# MiniSTM32_1.net
KiCad netlist of a schematic drawn in Altium Designer
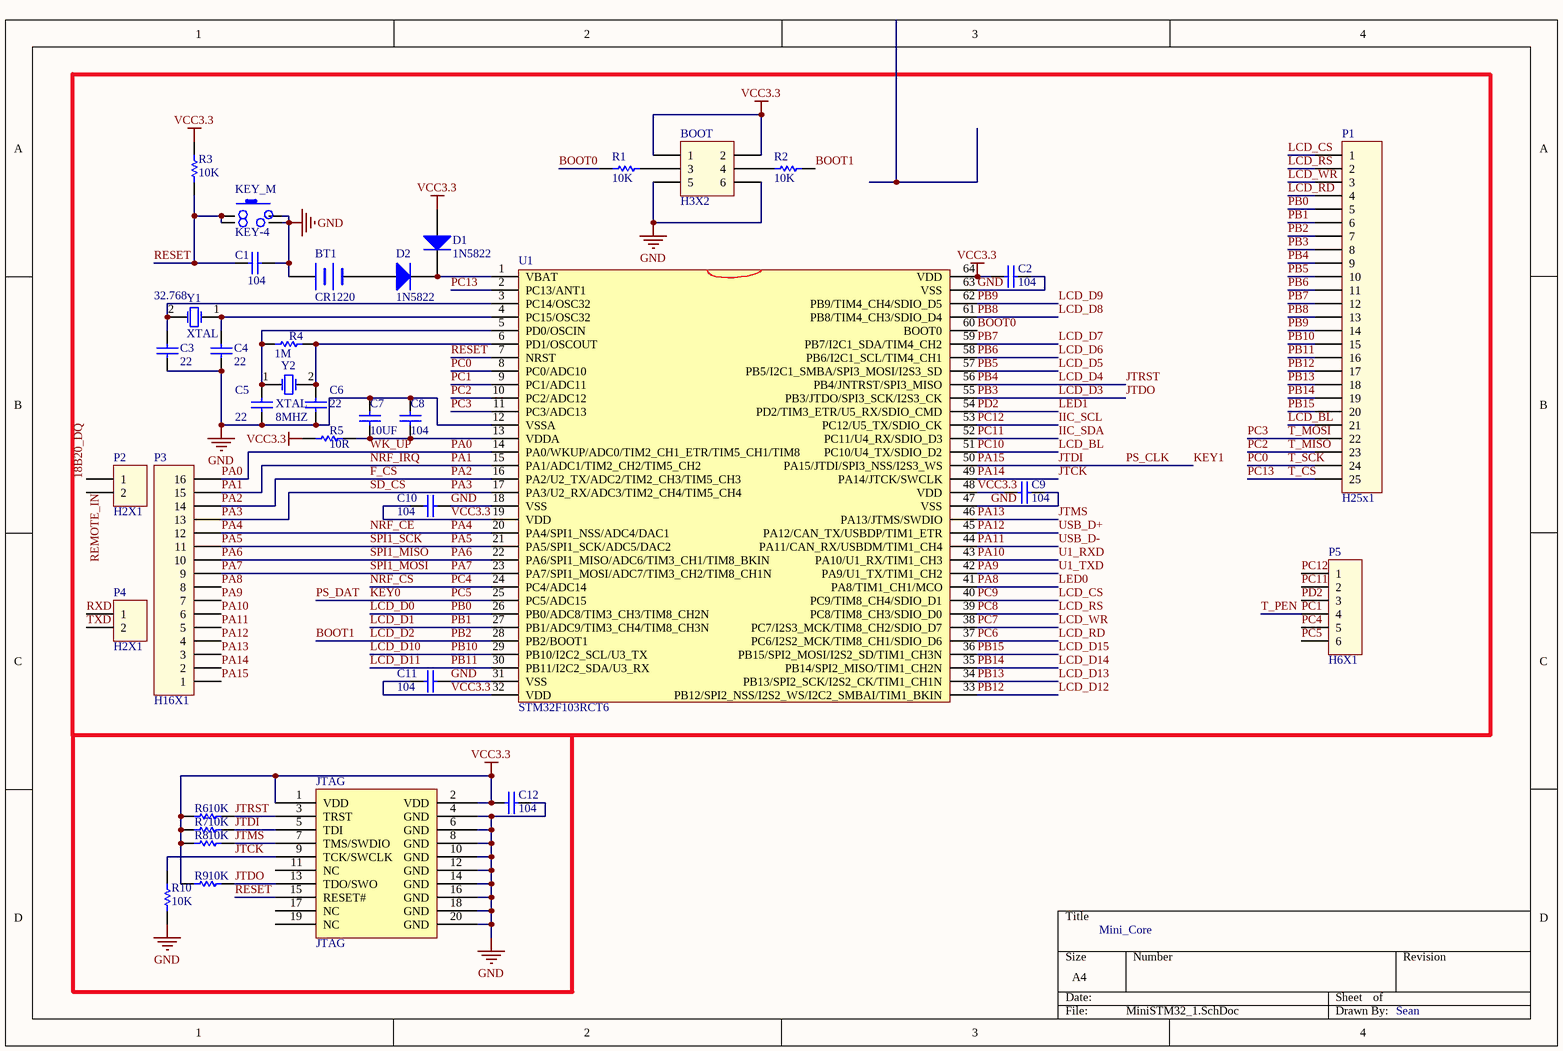
[diagram p0: MiniSTM32_1.SchDoc]

(export (version "E")
  (design (tool "Eeschema 10.0.6"))
  (components
    (comp (ref "BOOT") (value "H3X2") (footprint "H2.54-2X3") (libsource (lib "Sean") (part "H3X2")))
    (comp (ref "BT1") (value "CR1220") (footprint "CR1220") (libsource (lib "Sean") (part "BATTERY")))
    (comp (ref "C1")
      (value "Cap")
      (footprint "CAP[0603]")
      (fields (field (name "ALTIUM_UNNAMED_1") "104"))
      (libsource (lib "Sean") (part "Cap"))
    )
    (comp (ref "C2")
      (value "Cap")
      (footprint "CAP[0603]")
      (fields (field (name "ALTIUM_UNNAMED_1") "104"))
      (libsource (lib "Sean") (part "Cap"))
    )
    (comp (ref "C3")
      (value "Cap")
      (footprint "CAP[0603]")
      (fields (field (name "ALTIUM_UNNAMED_1") "22"))
      (libsource (lib "Sean") (part "Cap"))
    )
    (comp (ref "C4")
      (value "Cap")
      (footprint "CAP[0603]")
      (fields (field (name "ALTIUM_UNNAMED_1") "22"))
      (libsource (lib "Sean") (part "Cap"))
    )
    (comp (ref "C5")
      (value "Cap")
      (footprint "CAP[0805]")
      (fields (field (name "ALTIUM_UNNAMED_1") "22"))
      (libsource (lib "Sean") (part "Cap"))
    )
    (comp (ref "C6")
      (value "Cap")
      (footprint "CAP[0805]")
      (fields (field (name "ALTIUM_UNNAMED_1") "22"))
      (libsource (lib "Sean") (part "Cap"))
    )
    (comp (ref "C7")
      (value "Cap")
      (footprint "CAP[1206]")
      (fields (field (name "ALTIUM_UNNAMED_1") "10UF"))
      (libsource (lib "Sean") (part "Cap"))
    )
    (comp (ref "C8")
      (value "Cap")
      (footprint "CAP[0603]")
      (fields (field (name "ALTIUM_UNNAMED_1") "104"))
      (libsource (lib "Sean") (part "Cap"))
    )
    (comp (ref "C9")
      (value "Cap")
      (footprint "CAP[0603]")
      (fields (field (name "ALTIUM_UNNAMED_1") "104"))
      (libsource (lib "Sean") (part "Cap"))
    )
    (comp (ref "C10")
      (value "Cap")
      (footprint "CAP[0603]")
      (fields (field (name "ALTIUM_UNNAMED_1") "104"))
      (libsource (lib "Sean") (part "Cap"))
    )
    (comp (ref "C11")
      (value "Cap")
      (footprint "CAP[0603]")
      (fields (field (name "ALTIUM_UNNAMED_1") "104"))
      (libsource (lib "Sean") (part "Cap"))
    )
    (comp (ref "C12")
      (value "Cap")
      (footprint "CAP[0603]")
      (fields (field (name "ALTIUM_UNNAMED_1") "104"))
      (libsource (lib "Sean") (part "Cap"))
    )
    (comp (ref "D1") (value "1N5822") (footprint "1N4733") (libsource (lib "Sean") (part "1N5822")))
    (comp (ref "D2") (value "1N5822") (footprint "1N4733") (libsource (lib "Sean") (part "1N5822")))
    (comp (ref "JTAG") (value "JTAG") (footprint "JTAG") (libsource (lib "Sean") (part "JTAG")))
    (comp (ref "KEY_M") (value "KEY-4") (footprint "KEY-4(DIP)") (libsource (lib "Sean") (part "KEY-4")))
    (comp (ref "P1") (value "H25x1") (footprint "H2.54-1X25") (libsource (lib "Sean") (part "H25x1")))
    (comp (ref "P2") (value "H2X1") (footprint "H2.54-1X2") (libsource (lib "Sean") (part "H2X1")))
    (comp (ref "P3") (value "H16X1") (footprint "H2.54-1X16") (libsource (lib "Sean") (part "H16X1")))
    (comp (ref "P4") (value "H2X1") (footprint "H2.54-1X2") (libsource (lib "Sean") (part "H2X1")))
    (comp (ref "P5") (value "H6X1") (footprint "H2.54-1X6") (libsource (lib "Sean") (part "H6X1")))
    (comp (ref "R1")
      (value "Res")
      (footprint "RES[0603]")
      (fields (field (name "ALTIUM_UNNAMED_1") "10K"))
      (libsource (lib "Sean") (part "Res"))
    )
    (comp (ref "R2")
      (value "Res")
      (footprint "RES[0603]")
      (fields (field (name "ALTIUM_UNNAMED_1") "10K"))
      (libsource (lib "Sean") (part "Res"))
    )
    (comp (ref "R3")
      (value "Res")
      (footprint "RES[0603]")
      (fields (field (name "ALTIUM_UNNAMED_1") "10K"))
      (libsource (lib "Sean") (part "Res"))
    )
    (comp (ref "R4")
      (value "Res")
      (footprint "RES[0603]")
      (fields (field (name "ALTIUM_UNNAMED_1") "1M"))
      (libsource (lib "Sean") (part "Res"))
    )
    (comp (ref "R5")
      (value "Res")
      (footprint "RES[0603]")
      (fields (field (name "ALTIUM_UNNAMED_1") "10R"))
      (libsource (lib "Sean") (part "Res"))
    )
    (comp (ref "R6")
      (value "Res")
      (footprint "RES[0603]")
      (fields (field (name "ALTIUM_UNNAMED_1") "10K"))
      (libsource (lib "Sean") (part "Res"))
    )
    (comp (ref "R7")
      (value "Res")
      (footprint "RES[0603]")
      (fields (field (name "ALTIUM_UNNAMED_1") "10K"))
      (libsource (lib "Sean") (part "Res"))
    )
    (comp (ref "R8")
      (value "Res")
      (footprint "RES[0603]")
      (fields (field (name "ALTIUM_UNNAMED_1") "10K"))
      (libsource (lib "Sean") (part "Res"))
    )
    (comp (ref "R9")
      (value "Res")
      (footprint "RES[0603]")
      (fields (field (name "ALTIUM_UNNAMED_1") "10K"))
      (libsource (lib "Sean") (part "Res"))
    )
    (comp (ref "R10")
      (value "Res")
      (footprint "RES[0603]")
      (fields (field (name "ALTIUM_UNNAMED_1") "10K"))
      (libsource (lib "Sean") (part "Res"))
    )
    (comp (ref "U1")
      (value "STM32F103RCT6")
      (footprint "LQFP-64")
      (libsource (lib "Sean") (part "STM32F103RCT6"))
    )
    (comp (ref "Y1")
      (value "XTAL")
      (footprint "XTAL-32768_2")
      (fields (field (name "ALTIUM_UNNAMED_1") "32.768"))
      (libsource (lib "Sean") (part "XTAL"))
    )
    (comp (ref "Y2")
      (value "XTAL")
      (footprint "XTAL")
      (fields (field (name "ALTIUM_UNNAMED_1") "8MHZ"))
      (libsource (lib "Sean") (part "XTAL"))
    )
  )
  (nets
    (net (code "1") (name "/18B20_DQ") (class "Default")
      (node (ref "P2") (pin "1") (pinfunction "1_1") (pintype "passive"))
    )
    (net (code "2") (name "/BOOT0") (class "Default")
      (node (ref "R1") (pin "1") (pinfunction "1_1") (pintype "passive"))
      (node (ref "U1") (pin "60") (pinfunction "BOOT0_60") (pintype "passive"))
    )
    (net (code "3") (name "/BOOT1") (class "Default")
      (node (ref "P1") (pin "7") (pinfunction "7_7") (pintype "passive"))
      (node (ref "R2") (pin "2") (pinfunction "2_2") (pintype "passive"))
      (node (ref "U1") (pin "28") (pinfunction "PB2/BOOT1_28") (pintype "passive"))
    )
    (net (code "4") (name "/F_CS") (class "Default")
      (node (ref "P3") (pin "14") (pinfunction "14_14") (pintype "passive"))
      (node (ref "U1") (pin "16") (pinfunction "PA2/U2_TX/ADC2/TIM2_CH3/TIM5_CH3_16") (pintype "passive"))
    )
    (net (code "5") (name "/IIC_SCL") (class "Default")
      (node (ref "P5") (pin "1") (pinfunction "1_1") (pintype "passive"))
      (node (ref "U1") (pin "53") (pinfunction "PC12/U5_TX/SDIO_CK_53") (pintype "passive"))
    )
    (net (code "6") (name "/IIC_SDA") (class "Default")
      (node (ref "P5") (pin "2") (pinfunction "2_2") (pintype "passive"))
      (node (ref "U1") (pin "52") (pinfunction "PC11/U4_RX/SDIO_D3_52") (pintype "passive"))
    )
    (net (code "7") (name "/JTCK") (class "Default")
      (node (ref "JTAG") (pin "9") (pinfunction "TCK/SWCLK_9") (pintype "passive"))
      (node (ref "P3") (pin "2") (pinfunction "2_2") (pintype "passive"))
      (node (ref "R10") (pin "1") (pinfunction "1_1") (pintype "passive"))
      (node (ref "U1") (pin "49") (pinfunction "PA14/JTCK/SWCLK_49") (pintype "passive"))
    )
    (net (code "8") (name "/JTDI") (class "Default")
      (node (ref "JTAG") (pin "5") (pinfunction "TDI_5") (pintype "passive"))
      (node (ref "P3") (pin "1") (pinfunction "1_1") (pintype "passive"))
      (node (ref "R7") (pin "1") (pinfunction "1_1") (pintype "passive"))
      (node (ref "U1") (pin "50") (pinfunction "PA15/JTDI/SPI3_NSS/I2S3_WS_50") (pintype "passive"))
    )
    (net (code "9") (name "/JTDO") (class "Default")
      (node (ref "JTAG") (pin "13") (pinfunction "TDO/SWO_13") (pintype "passive"))
      (node (ref "P1") (pin "8") (pinfunction "8_8") (pintype "passive"))
      (node (ref "R9") (pin "1") (pinfunction "1_1") (pintype "passive"))
      (node (ref "U1") (pin "55") (pinfunction "PB3/JTDO/SPI3_SCK/I2S3_CK_55") (pintype "passive"))
    )
    (net (code "10") (name "/JTMS") (class "Default")
      (node (ref "JTAG") (pin "7") (pinfunction "TMS/SWDIO_7") (pintype "passive"))
      (node (ref "P3") (pin "3") (pinfunction "3_3") (pintype "passive"))
      (node (ref "R8") (pin "1") (pinfunction "1_1") (pintype "passive"))
      (node (ref "U1") (pin "46") (pinfunction "PA13/JTMS/SWDIO_46") (pintype "passive"))
    )
    (net (code "11") (name "/JTRST") (class "Default")
      (node (ref "JTAG") (pin "3") (pinfunction "TRST_3") (pintype "passive"))
      (node (ref "P1") (pin "9") (pinfunction "9_9") (pintype "passive"))
      (node (ref "R6") (pin "1") (pinfunction "1_1") (pintype "passive"))
      (node (ref "U1") (pin "56") (pinfunction "PB4/JNTRST/SPI3_MISO_56") (pintype "passive"))
    )
    (net (code "12") (name "/KEY0") (class "Default")
      (node (ref "P5") (pin "6") (pinfunction "6_6") (pintype "passive"))
      (node (ref "U1") (pin "25") (pinfunction "PC5/ADC15_25") (pintype "passive"))
    )
    (net (code "13") (name "/LCD_BL") (class "Default")
      (node (ref "P1") (pin "21") (pinfunction "21_21") (pintype "passive"))
      (node (ref "U1") (pin "51") (pinfunction "PC10/U4_TX/SDIO_D2_51") (pintype "passive"))
    )
    (net (code "14") (name "/LCD_CS") (class "Default")
      (node (ref "P1") (pin "1") (pinfunction "1_1") (pintype "passive"))
      (node (ref "U1") (pin "40") (pinfunction "PC9/TIM8_CH4/SDIO_D1_40") (pintype "passive"))
    )
    (net (code "15") (name "/LCD_D0") (class "Default")
      (node (ref "P1") (pin "5") (pinfunction "5_5") (pintype "passive"))
      (node (ref "U1") (pin "26") (pinfunction "PB0/ADC8/TIM3_CH3/TIM8_CH2N_26") (pintype "passive"))
    )
    (net (code "16") (name "/LCD_D1") (class "Default")
      (node (ref "P1") (pin "6") (pinfunction "6_6") (pintype "passive"))
      (node (ref "U1") (pin "27") (pinfunction "PB1/ADC9/TIM3_CH4/TIM8_CH3N_27") (pintype "passive"))
    )
    (net (code "17") (name "/LCD_D5") (class "Default")
      (node (ref "P1") (pin "10") (pinfunction "10_10") (pintype "passive"))
      (node (ref "U1") (pin "57") (pinfunction "PB5/I2C1_SMBA/SPI3_MOSI/I2S3_SD_57") (pintype "passive"))
    )
    (net (code "18") (name "/LCD_D6") (class "Default")
      (node (ref "P1") (pin "11") (pinfunction "11_11") (pintype "passive"))
      (node (ref "U1") (pin "58") (pinfunction "PB6/I2C1_SCL/TIM4_CH1_58") (pintype "passive"))
    )
    (net (code "19") (name "/LCD_D7") (class "Default")
      (node (ref "P1") (pin "12") (pinfunction "12_12") (pintype "passive"))
      (node (ref "U1") (pin "59") (pinfunction "PB7/I2C1_SDA/TIM4_CH2_59") (pintype "passive"))
    )
    (net (code "20") (name "/LCD_D8") (class "Default")
      (node (ref "P1") (pin "13") (pinfunction "13_13") (pintype "passive"))
      (node (ref "U1") (pin "61") (pinfunction "PB8/TIM4_CH3/SDIO_D4_61") (pintype "passive"))
    )
    (net (code "21") (name "/LCD_D9") (class "Default")
      (node (ref "P1") (pin "14") (pinfunction "14_14") (pintype "passive"))
      (node (ref "U1") (pin "62") (pinfunction "PB9/TIM4_CH4/SDIO_D5_62") (pintype "passive"))
    )
    (net (code "22") (name "/LCD_D10") (class "Default")
      (node (ref "P1") (pin "15") (pinfunction "15_15") (pintype "passive"))
      (node (ref "U1") (pin "29") (pinfunction "PB10/I2C2_SCL/U3_TX_29") (pintype "passive"))
    )
    (net (code "23") (name "/LCD_D11") (class "Default")
      (node (ref "P1") (pin "16") (pinfunction "16_16") (pintype "passive"))
      (node (ref "U1") (pin "30") (pinfunction "PB11/I2C2_SDA/U3_RX_30") (pintype "passive"))
    )
    (net (code "24") (name "/LCD_D12") (class "Default")
      (node (ref "P1") (pin "17") (pinfunction "17_17") (pintype "passive"))
      (node (ref "U1") (pin "33") (pinfunction "PB12/SPI2_NSS/I2S2_WS/I2C2_SMBAI/TIM1_BKIN_33") (pintype "passive"))
    )
    (net (code "25") (name "/LCD_D13") (class "Default")
      (node (ref "P1") (pin "18") (pinfunction "18_18") (pintype "passive"))
      (node (ref "U1") (pin "34") (pinfunction "PB13/SPI2_SCK/I2S2_CK/TIM1_CH1N_34") (pintype "passive"))
    )
    (net (code "26") (name "/LCD_D14") (class "Default")
      (node (ref "P1") (pin "19") (pinfunction "19_19") (pintype "passive"))
      (node (ref "U1") (pin "35") (pinfunction "PB14/SPI2_MISO/TIM1_CH2N_35") (pintype "passive"))
    )
    (net (code "27") (name "/LCD_D15") (class "Default")
      (node (ref "P1") (pin "20") (pinfunction "20_20") (pintype "passive"))
      (node (ref "U1") (pin "36") (pinfunction "PB15/SPI2_MOSI/I2S2_SD/TIM1_CH3N_36") (pintype "passive"))
    )
    (net (code "28") (name "/LCD_RD") (class "Default")
      (node (ref "P1") (pin "4") (pinfunction "4_4") (pintype "passive"))
      (node (ref "U1") (pin "37") (pinfunction "PC6/I2S2_MCK/TIM8_CH1/SDIO_D6_37") (pintype "passive"))
    )
    (net (code "29") (name "/LCD_RS") (class "Default")
      (node (ref "P1") (pin "2") (pinfunction "2_2") (pintype "passive"))
      (node (ref "U1") (pin "39") (pinfunction "PC8/TIM8_CH3/SDIO_D0_39") (pintype "passive"))
    )
    (net (code "30") (name "/LCD_WR") (class "Default")
      (node (ref "P1") (pin "3") (pinfunction "3_3") (pintype "passive"))
      (node (ref "U1") (pin "38") (pinfunction "PC7/I2S3_MCK/TIM8_CH2/SDIO_D7_38") (pintype "passive"))
    )
    (net (code "31") (name "/LED0") (class "Default")
      (node (ref "P3") (pin "8") (pinfunction "8_8") (pintype "passive"))
      (node (ref "U1") (pin "41") (pinfunction "PA8/TIM1_CH1/MCO_41") (pintype "passive"))
    )
    (net (code "32") (name "/LED1") (class "Default")
      (node (ref "P5") (pin "3") (pinfunction "3_3") (pintype "passive"))
      (node (ref "U1") (pin "54") (pinfunction "PD2/TIM3_ETR/U5_RX/SDIO_CMD_54") (pintype "passive"))
    )
    (net (code "33") (name "/NRF_CE") (class "Default")
      (node (ref "P3") (pin "12") (pinfunction "12_12") (pintype "passive"))
      (node (ref "U1") (pin "20") (pinfunction "PA4/SPI1_NSS/ADC4/DAC1_20") (pintype "passive"))
    )
    (net (code "34") (name "/NRF_CS") (class "Default")
      (node (ref "P5") (pin "5") (pinfunction "5_5") (pintype "passive"))
      (node (ref "U1") (pin "24") (pinfunction "PC4/ADC14_24") (pintype "passive"))
    )
    (net (code "35") (name "/NRF_IRQ") (class "Default")
      (node (ref "P3") (pin "15") (pinfunction "15_15") (pintype "passive"))
      (node (ref "U1") (pin "15") (pinfunction "PA1/ADC1/TIM2_CH2/TIM5_CH2_15") (pintype "passive"))
    )
    (net (code "36") (name "/PA0") (class "Default")
      (node (ref "P3") (pin "16") (pinfunction "16_16") (pintype "passive"))
      (node (ref "U1") (pin "14") (pinfunction "PA0/WKUP/ADC0/TIM2_CH1_ETR/TIM5_CH1/TIM8_14") (pintype "passive"))
    )
    (net (code "37") (name "/PA3") (class "Default")
      (node (ref "P3") (pin "13") (pinfunction "13_13") (pintype "passive"))
      (node (ref "U1") (pin "17") (pinfunction "PA3/U2_RX/ADC3/TIM2_CH4/TIM5_CH4_17") (pintype "passive"))
    )
    (net (code "38") (name "/PA5") (class "Default")
      (node (ref "P3") (pin "11") (pinfunction "11_11") (pintype "passive"))
      (node (ref "U1") (pin "21") (pinfunction "PA5/SPI1_SCK/ADC5/DAC2_21") (pintype "passive"))
    )
    (net (code "39") (name "/PA6") (class "Default")
      (node (ref "P3") (pin "10") (pinfunction "10_10") (pintype "passive"))
      (node (ref "U1") (pin "22") (pinfunction "PA6/SPI1_MISO/ADC6/TIM3_CH1/TIM8_BKIN_22") (pintype "passive"))
    )
    (net (code "40") (name "/PA7") (class "Default")
      (node (ref "P3") (pin "9") (pinfunction "9_9") (pintype "passive"))
      (node (ref "U1") (pin "23") (pinfunction "PA7/SPI1_MOSI/ADC7/TIM3_CH2/TIM8_CH1N_23") (pintype "passive"))
    )
    (net (code "41") (name "/PA9") (class "Default")
      (node (ref "P3") (pin "7") (pinfunction "7_7") (pintype "passive"))
      (node (ref "U1") (pin "42") (pinfunction "PA9/U1_TX/TIM1_CH2_42") (pintype "passive"))
    )
    (net (code "42") (name "/PA10") (class "Default")
      (node (ref "P3") (pin "6") (pinfunction "6_6") (pintype "passive"))
      (node (ref "U1") (pin "43") (pinfunction "PA10/U1_RX/TIM1_CH3_43") (pintype "passive"))
    )
    (net (code "43") (name "/PA11") (class "Default")
      (node (ref "P3") (pin "5") (pinfunction "5_5") (pintype "passive"))
      (node (ref "U1") (pin "44") (pinfunction "PA11/CAN_RX/USBDM/TIM1_CH4_44") (pintype "passive"))
    )
    (net (code "44") (name "/PA12") (class "Default")
      (node (ref "P3") (pin "4") (pinfunction "4_4") (pintype "passive"))
      (node (ref "U1") (pin "45") (pinfunction "PA12/CAN_TX/USBDP/TIM1_ETR_45") (pintype "passive"))
    )
    (net (code "45") (name "/PC0") (class "Default")
      (node (ref "P1") (pin "24") (pinfunction "24_24") (pintype "passive"))
      (node (ref "U1") (pin "8") (pinfunction "PC0/ADC10_8") (pintype "passive"))
    )
    (net (code "46") (name "/PC1") (class "Default")
      (node (ref "P5") (pin "4") (pinfunction "4_4") (pintype "passive"))
      (node (ref "U1") (pin "9") (pinfunction "PC1/ADC11_9") (pintype "passive"))
    )
    (net (code "47") (name "/PC2") (class "Default")
      (node (ref "P1") (pin "23") (pinfunction "23_23") (pintype "passive"))
      (node (ref "U1") (pin "10") (pinfunction "PC2/ADC12_10") (pintype "passive"))
    )
    (net (code "48") (name "/PC3") (class "Default")
      (node (ref "P1") (pin "22") (pinfunction "22_22") (pintype "passive"))
      (node (ref "U1") (pin "11") (pinfunction "PC3/ADC13_11") (pintype "passive"))
    )
    (net (code "49") (name "/PC13") (class "Default")
      (node (ref "P1") (pin "25") (pinfunction "25_25") (pintype "passive"))
      (node (ref "U1") (pin "2") (pinfunction "PC13/ANT1_2") (pintype "passive"))
    )
    (net (code "50") (name "/REMOTE_IN") (class "Default")
      (node (ref "P2") (pin "2") (pinfunction "2_2") (pintype "passive"))
    )
    (net (code "51") (name "/RESET") (class "Default")
      (node (ref "C1") (pin "1") (pinfunction "1_1") (pintype "passive"))
      (node (ref "JTAG") (pin "15") (pinfunction "RESET#_15") (pintype "passive"))
      (node (ref "KEY_M") (pin "1") (pinfunction "1_1") (pintype "passive"))
      (node (ref "KEY_M") (pin "2") (pinfunction "2_2") (pintype "passive"))
      (node (ref "R3") (pin "1") (pinfunction "1_1") (pintype "passive"))
      (node (ref "U1") (pin "7") (pinfunction "NRST_7") (pintype "passive"))
    )
    (net (code "52") (name "/RXD") (class "Default")
      (node (ref "P4") (pin "1") (pinfunction "1_1") (pintype "passive"))
    )
    (net (code "53") (name "/TXD") (class "Default")
      (node (ref "P4") (pin "2") (pinfunction "2_2") (pintype "passive"))
    )
    (net (code "54") (name "GND") (class "Default")
      (node (ref "BOOT") (pin "5") (pinfunction "5_5") (pintype "passive"))
      (node (ref "BOOT") (pin "6") (pinfunction "6_6") (pintype "passive"))
      (node (ref "BT1") (pin "1") (pinfunction "+_1") (pintype "passive"))
      (node (ref "C1") (pin "2") (pinfunction "2_2") (pintype "passive"))
      (node (ref "C10") (pin "1") (pinfunction "1_1") (pintype "passive"))
      (node (ref "C11") (pin "1") (pinfunction "1_1") (pintype "passive"))
      (node (ref "C12") (pin "1") (pinfunction "1_1") (pintype "passive"))
      (node (ref "C2") (pin "2") (pinfunction "2_2") (pintype "passive"))
      (node (ref "C3") (pin "1") (pinfunction "1_1") (pintype "passive"))
      (node (ref "C4") (pin "1") (pinfunction "1_1") (pintype "passive"))
      (node (ref "C5") (pin "1") (pinfunction "1_1") (pintype "passive"))
      (node (ref "C6") (pin "1") (pinfunction "1_1") (pintype "passive"))
      (node (ref "C7") (pin "2") (pinfunction "2_2") (pintype "passive"))
      (node (ref "C8") (pin "2") (pinfunction "2_2") (pintype "passive"))
      (node (ref "C9") (pin "2") (pinfunction "2_2") (pintype "passive"))
      (node (ref "JTAG") (pin "10") (pinfunction "GND_10") (pintype "passive"))
      (node (ref "JTAG") (pin "12") (pinfunction "GND_12") (pintype "passive"))
      (node (ref "JTAG") (pin "14") (pinfunction "GND_14") (pintype "passive"))
      (node (ref "JTAG") (pin "16") (pinfunction "GND_16") (pintype "passive"))
      (node (ref "JTAG") (pin "18") (pinfunction "GND_18") (pintype "passive"))
      (node (ref "JTAG") (pin "20") (pinfunction "GND_20") (pintype "passive"))
      (node (ref "JTAG") (pin "4") (pinfunction "GND_4") (pintype "passive"))
      (node (ref "JTAG") (pin "6") (pinfunction "GND_6") (pintype "passive"))
      (node (ref "JTAG") (pin "8") (pinfunction "GND_8") (pintype "passive"))
      (node (ref "KEY_M") (pin "3") (pinfunction "3_3") (pintype "passive"))
      (node (ref "KEY_M") (pin "4") (pinfunction "4_4") (pintype "passive"))
      (node (ref "R10") (pin "2") (pinfunction "2_2") (pintype "passive"))
      (node (ref "U1") (pin "12") (pinfunction "VSSA_12") (pintype "passive"))
      (node (ref "U1") (pin "18") (pinfunction "VSS_18") (pintype "passive"))
      (node (ref "U1") (pin "31") (pinfunction "VSS_31") (pintype "passive"))
      (node (ref "U1") (pin "47") (pinfunction "VSS_47") (pintype "passive"))
      (node (ref "U1") (pin "63") (pinfunction "VSS_63") (pintype "passive"))
    )
    (net (code "55") (name "Net-(BOOT-Pad3)") (class "Default")
      (node (ref "BOOT") (pin "3") (pinfunction "3_3") (pintype "passive"))
      (node (ref "R1") (pin "2") (pinfunction "2_2") (pintype "passive"))
    )
    (net (code "56") (name "Net-(BOOT-Pad4)") (class "Default")
      (node (ref "BOOT") (pin "4") (pinfunction "4_4") (pintype "passive"))
      (node (ref "R2") (pin "1") (pinfunction "1_1") (pintype "passive"))
    )
    (net (code "57") (name "Net-(BT1--)") (class "Default")
      (node (ref "BT1") (pin "2") (pinfunction "-_2") (pintype "passive"))
      (node (ref "D2") (pin "1") (pinfunction "A_1") (pintype "passive"))
    )
    (net (code "58") (name "Net-(D1-K)") (class "Default")
      (node (ref "D1") (pin "2") (pinfunction "K_2") (pintype "passive"))
      (node (ref "D2") (pin "2") (pinfunction "K_2") (pintype "passive"))
      (node (ref "U1") (pin "1") (pinfunction "VBAT_1") (pintype "passive"))
    )
    (net (code "59") (name "Net-(U1-PC14{slash}OSC32)") (class "Default")
      (node (ref "C3") (pin "2") (pinfunction "2_2") (pintype "passive"))
      (node (ref "U1") (pin "3") (pinfunction "PC14/OSC32_3") (pintype "passive"))
      (node (ref "Y1") (pin "2") (pinfunction "OSC2_2") (pintype "passive"))
    )
    (net (code "60") (name "Net-(U1-PC15{slash}OSC32)") (class "Default")
      (node (ref "C4") (pin "2") (pinfunction "2_2") (pintype "passive"))
      (node (ref "U1") (pin "4") (pinfunction "PC15/OSC32_4") (pintype "passive"))
      (node (ref "Y1") (pin "1") (pinfunction "OSC1_1") (pintype "passive"))
    )
    (net (code "61") (name "Net-(U1-PD0{slash}OSCIN)") (class "Default")
      (node (ref "C5") (pin "2") (pinfunction "2_2") (pintype "passive"))
      (node (ref "R4") (pin "2") (pinfunction "2_2") (pintype "passive"))
      (node (ref "U1") (pin "5") (pinfunction "PD0/OSCIN_5") (pintype "passive"))
      (node (ref "Y2") (pin "1") (pinfunction "OSC1_1") (pintype "passive"))
    )
    (net (code "62") (name "Net-(U1-PD1{slash}OSCOUT)") (class "Default")
      (node (ref "C6") (pin "2") (pinfunction "2_2") (pintype "passive"))
      (node (ref "R4") (pin "1") (pinfunction "1_1") (pintype "passive"))
      (node (ref "U1") (pin "6") (pinfunction "PD1/OSCOUT_6") (pintype "passive"))
      (node (ref "Y2") (pin "2") (pinfunction "OSC2_2") (pintype "passive"))
    )
    (net (code "63") (name "Net-(U1-VDDA)") (class "Default")
      (node (ref "C7") (pin "1") (pinfunction "1_1") (pintype "passive"))
      (node (ref "C8") (pin "1") (pinfunction "1_1") (pintype "passive"))
      (node (ref "R5") (pin "1") (pinfunction "1_1") (pintype "passive"))
      (node (ref "U1") (pin "13") (pinfunction "VDDA_13") (pintype "passive"))
    )
    (net (code "64") (name "VCC3.3") (class "Default")
      (node (ref "BOOT") (pin "1") (pinfunction "1_1") (pintype "passive"))
      (node (ref "BOOT") (pin "2") (pinfunction "2_2") (pintype "passive"))
      (node (ref "C10") (pin "2") (pinfunction "2_2") (pintype "passive"))
      (node (ref "C11") (pin "2") (pinfunction "2_2") (pintype "passive"))
      (node (ref "C12") (pin "2") (pinfunction "2_2") (pintype "passive"))
      (node (ref "C2") (pin "1") (pinfunction "1_1") (pintype "passive"))
      (node (ref "C9") (pin "1") (pinfunction "1_1") (pintype "passive"))
      (node (ref "D1") (pin "1") (pinfunction "A_1") (pintype "passive"))
      (node (ref "JTAG") (pin "1") (pinfunction "VDD_1") (pintype "passive"))
      (node (ref "JTAG") (pin "2") (pinfunction "VDD_2") (pintype "passive"))
      (node (ref "R3") (pin "2") (pinfunction "2_2") (pintype "passive"))
      (node (ref "R5") (pin "2") (pinfunction "2_2") (pintype "passive"))
      (node (ref "R6") (pin "2") (pinfunction "2_2") (pintype "passive"))
      (node (ref "R7") (pin "2") (pinfunction "2_2") (pintype "passive"))
      (node (ref "R8") (pin "2") (pinfunction "2_2") (pintype "passive"))
      (node (ref "R9") (pin "2") (pinfunction "2_2") (pintype "passive"))
      (node (ref "U1") (pin "19") (pinfunction "VDD_19") (pintype "passive"))
      (node (ref "U1") (pin "32") (pinfunction "VDD_32") (pintype "passive"))
      (node (ref "U1") (pin "48") (pinfunction "VDD_48") (pintype "passive"))
      (node (ref "U1") (pin "64") (pinfunction "VDD_64") (pintype "passive"))
    )
    (net (code "65") (name "unconnected-(JTAG-NC-Pad11)") (class "Default")
      (node (ref "JTAG") (pin "11") (pinfunction "NC_11") (pintype "passive"))
    )
    (net (code "66") (name "unconnected-(JTAG-NC-Pad17)") (class "Default")
      (node (ref "JTAG") (pin "17") (pinfunction "NC_17") (pintype "passive"))
    )
    (net (code "67") (name "unconnected-(JTAG-NC-Pad19)") (class "Default")
      (node (ref "JTAG") (pin "19") (pinfunction "NC_19") (pintype "passive"))
    )
  )
)
